# BEP31_final_kopie.net
KiCad netlist of a schematic drawn in EAGLE
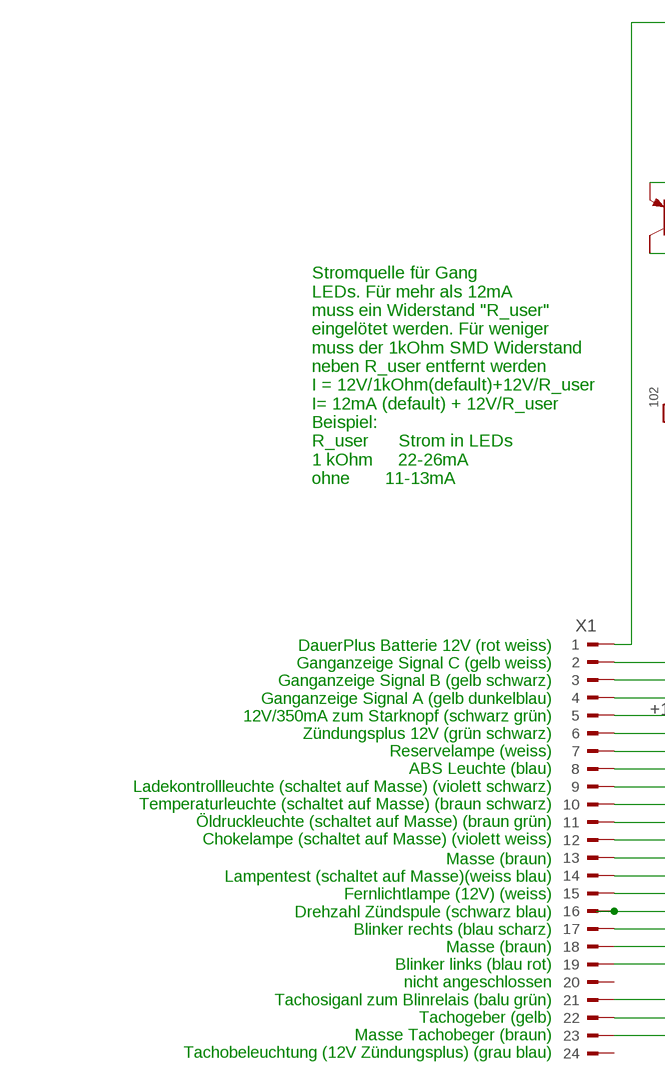
[diagram p0: schematic, sheet 1, part 1 of 2]
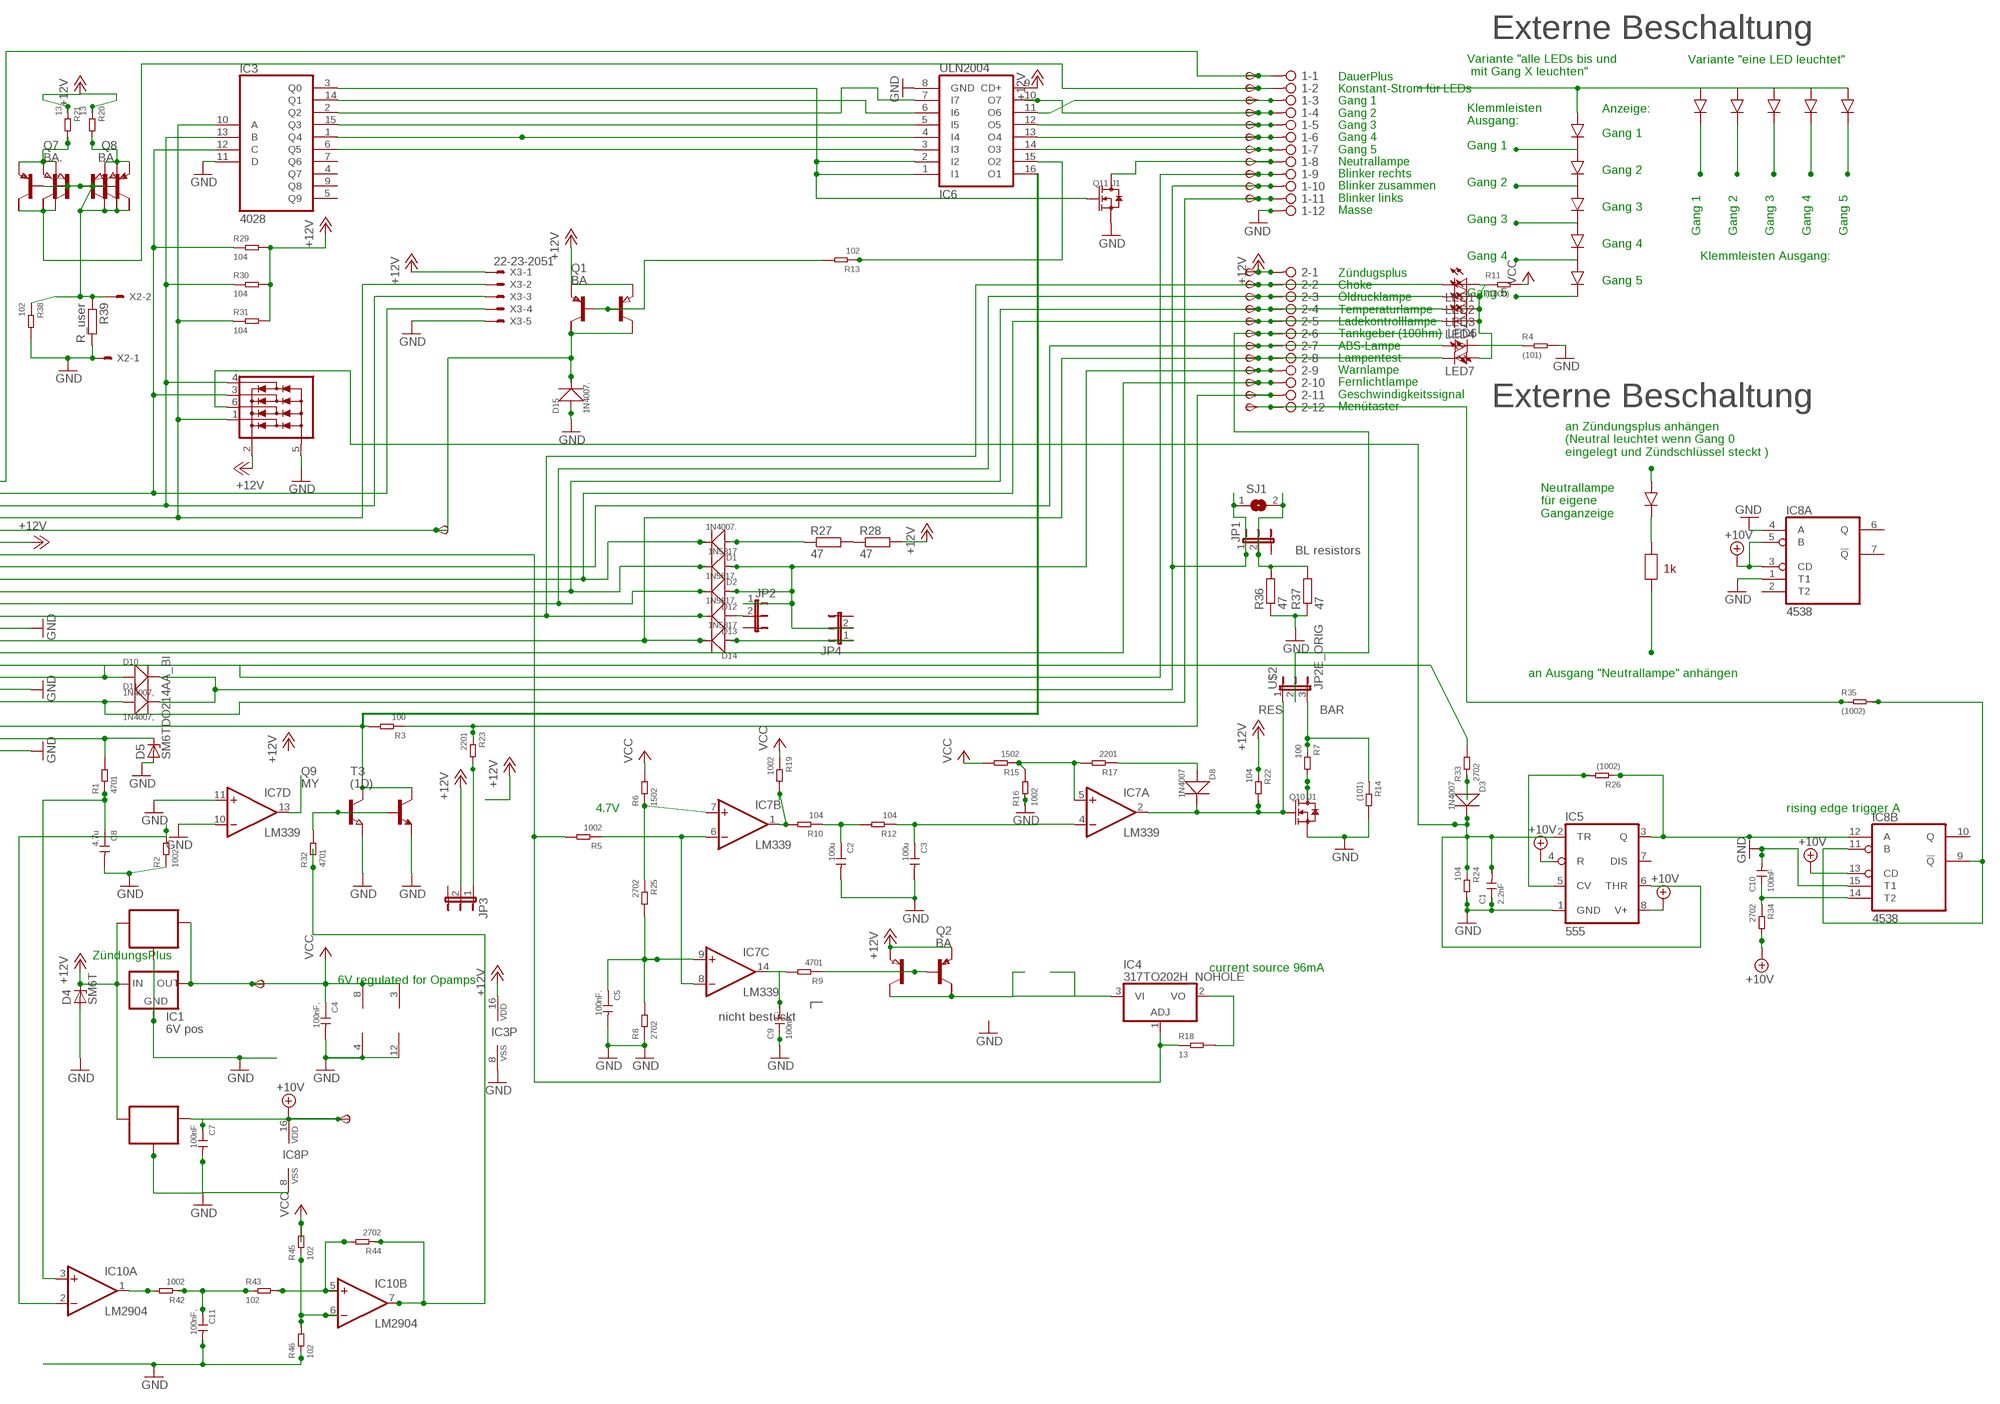
[diagram p1: schematic, sheet 1, part 2 of 2]

(export (version "E")
  (design (tool "Eeschema 10.0.6"))
  (components
    (comp (ref "1")
      (value "2081-1132")
      (footprint "eagle-import:12-PIN")
      (libsource (lib "eagle-import") (part "2081-1132"))
    )
    (comp (ref "2")
      (value "2081-1132")
      (footprint "eagle-import:12-PIN")
      (libsource (lib "eagle-import") (part "2081-1132"))
    )
    (comp (ref "6V")
      (value "TPSB2.0")
      (footprint "eagle-import:B2.0")
      (libsource (lib "eagle-import") (part "TPSB2.0"))
    )
    (comp (ref "10V")
      (value "TPSB2.0")
      (footprint "eagle-import:B2.0")
      (libsource (lib "eagle-import") (part "TPSB2.0"))
    )
    (comp (ref "C1")
      (value "2.2nF")
      (footprint "eagle-import:C0805")
      (fields (field (name "MPN") "CC0805KRX7R9BB104"))
      (libsource (lib "eagle-import") (part "CERAMIC-100NF-50V-10%-X7R(0805)"))
    )
    (comp (ref "C2")
      (value "100u")
      (footprint "eagle-import:C1206")
      (fields (field (name "MPN") "GRM31CR60J107ME39L"))
      (libsource (lib "eagle-import") (part "CERAMIC-100UF-6.3V-20%-X5R(1206)"))
    )
    (comp (ref "C3")
      (value "100u")
      (footprint "eagle-import:C1206")
      (fields (field (name "MPN") "GRM31CR60J107ME39L"))
      (libsource (lib "eagle-import") (part "CERAMIC-100UF-6.3V-20%-X5R(1206)"))
    )
    (comp (ref "C4")
      (value "100nF,")
      (footprint "eagle-import:C0805")
      (fields (field (name "MPN") "CC0805KRX7R9BB104"))
      (libsource (lib "eagle-import") (part "CERAMIC-100NF-50V-10%-X7R(0805)"))
    )
    (comp (ref "C5")
      (value "100nF.")
      (footprint "eagle-import:C0805")
      (fields (field (name "MPN") "CC0805KRX7R9BB104"))
      (libsource (lib "eagle-import") (part "CERAMIC-100NF-50V-10%-X7R(0805)"))
    )
    (comp (ref "C7")
      (value "100nF")
      (footprint "eagle-import:C0805")
      (fields (field (name "MPN") "CC0805KRX7R9BB104"))
      (libsource (lib "eagle-import") (part "CERAMIC-100NF-50V-10%-X7R(0805)"))
    )
    (comp (ref "C8")
      (value "4.7u")
      (footprint "eagle-import:C0805")
      (fields (field (name "MPN") "CC0805KKX5R8BB475"))
      (libsource (lib "eagle-import") (part "CERAMIC-4.7UF-25V-10%-X5R(0805)"))
    )
    (comp (ref "C9")
      (value "100nF.")
      (footprint "eagle-import:C0805")
      (fields (field (name "MPN") "CC0805KRX7R9BB104"))
      (libsource (lib "eagle-import") (part "CERAMIC-100NF-50V-10%-X7R(0805)"))
    )
    (comp (ref "C10")
      (value "100nF")
      (footprint "eagle-import:C0805")
      (fields (field (name "MPN") "CC0805KRX7R9BB104"))
      (libsource (lib "eagle-import") (part "CERAMIC-100NF-50V-10%-X7R(0805)"))
    )
    (comp (ref "C11")
      (value "100nF,")
      (footprint "eagle-import:C0805")
      (fields (field (name "MPN") "CC0805KRX7R9BB104"))
      (libsource (lib "eagle-import") (part "CERAMIC-100NF-50V-10%-X7R(0805)"))
    )
    (comp (ref "D1")
      (value "1N4007.")
      (footprint "eagle-import:DO-214AC")
      (fields (field (name "MPN") "1N4007"))
      (libsource (lib "eagle-import") (part "DIODE-GEN-PURPOSE-1KV-1A(DO-214AC)"))
    )
    (comp (ref "D2")
      (value "1N5817")
      (footprint "eagle-import:DO-214AC_SLIM")
      (libsource (lib "eagle-import") (part "DIODE-GEN-PURPOSE-1KV-1A(DO-214AC)DO-214AC/1206"))
    )
    (comp (ref "D3")
      (value "1N4007")
      (footprint "eagle-import:DO-214AC")
      (libsource (lib "eagle-import") (part "DIODE-GEN-PURPOSE-1KV-1A(DO-214AC)"))
    )
    (comp (ref "D4")
      (value "SM6T")
      (footprint "eagle-import:DO214AA")
      (libsource (lib "eagle-import") (part "SM6T"))
    )
    (comp (ref "D5")
      (value "SM6TDO214AA_BI")
      (footprint "eagle-import:DO214AA_BI")
      (libsource (lib "eagle-import") (part "SM6TDO214AA_BI"))
    )
    (comp (ref "D8")
      (value "1N4007")
      (footprint "eagle-import:DO-214AC")
      (libsource (lib "eagle-import") (part "DIODE-GEN-PURPOSE-1KV-1A(DO-214AC)"))
    )
    (comp (ref "D10")
      (value "1N4007,")
      (footprint "eagle-import:DO-214AC")
      (fields (field (name "MPN") "1N4007"))
      (libsource (lib "eagle-import") (part "DIODE-GEN-PURPOSE-1KV-1A(DO-214AC)"))
    )
    (comp (ref "D11")
      (value "1N4007,")
      (footprint "eagle-import:DO-214AC")
      (fields (field (name "MPN") "1N4007"))
      (libsource (lib "eagle-import") (part "DIODE-GEN-PURPOSE-1KV-1A(DO-214AC)"))
    )
    (comp (ref "D12")
      (value "1N5817.")
      (footprint "eagle-import:DO-214AC_SLIM")
      (libsource (lib "eagle-import") (part "DIODE-GEN-PURPOSE-1KV-1A(DO-214AC)DO-214AC/1206"))
    )
    (comp (ref "D13")
      (value "1N5817.")
      (footprint "eagle-import:DO-214AC_SLIM")
      (libsource (lib "eagle-import") (part "DIODE-GEN-PURPOSE-1KV-1A(DO-214AC)DO-214AC/1206"))
    )
    (comp (ref "D14")
      (value "1N5817")
      (footprint "eagle-import:DO-214AC_SLIM")
      (libsource (lib "eagle-import") (part "DIODE-GEN-PURPOSE-1KV-1A(DO-214AC)DO-214AC/1206"))
    )
    (comp (ref "D15")
      (value "1N4007.")
      (footprint "eagle-import:DO-214AC")
      (fields (field (name "MPN") "1N4007"))
      (libsource (lib "eagle-import") (part "DIODE-GEN-PURPOSE-1KV-1A(DO-214AC)"))
    )
    (comp (ref "IC1")
      (value "6V pos")
      (footprint "eagle-import:78LXX")
      (libsource (lib "eagle-import") (part "v-reg_78LXX"))
    )
    (comp (ref "IC2")
      (value "78L06")
      (footprint "eagle-import:SOT89_ROUND")
      (libsource (lib "eagle-import") (part "78LXXSOT89_ROUND"))
    )
    (comp (ref "IC3")
      (value "4028")
      (footprint "eagle-import:SO16")
      (libsource (lib "eagle-import") (part "4028D"))
    )
    (comp (ref "IC4")
      (value "317TO202H_NOHOLE")
      (footprint "eagle-import:TO220H_NOHOLE")
      (libsource (lib "eagle-import") (part "317TO202H_NOHOLE"))
    )
    (comp (ref "IC5")
      (value "555")
      (footprint "eagle-import:SO08")
      (libsource (lib "eagle-import") (part "555DNE"))
    )
    (comp (ref "IC6")
      (value "ULN2004")
      (footprint "eagle-import:SO16")
      (libsource (lib "eagle-import") (part "ULN2004AD"))
    )
    (comp (ref "IC7")
      (value "LM339")
      (footprint "eagle-import:SO14")
      (libsource (lib "eagle-import") (part "LM339D"))
    )
    (comp (ref "IC8")
      (value "4538")
      (footprint "eagle-import:SO16")
      (libsource (lib "eagle-import") (part "4538D"))
    )
    (comp (ref "IC9")
      (value "78L10")
      (footprint "eagle-import:SOT89_ROUND")
      (libsource (lib "eagle-import") (part "78LXXSOT89_ROUND"))
    )
    (comp (ref "IC10")
      (value "LM2904")
      (footprint "eagle-import:SO08")
      (libsource (lib "eagle-import") (part "LM358D"))
    )
    (comp (ref "JP1")
      (value "JP2EJP2_SMALLPADS")
      (footprint "eagle-import:JP2_SMALLPADS")
      (libsource (lib "eagle-import") (part "JP2EJP2_SMALLPADS"))
    )
    (comp (ref "JP2")
      (value "JP2EJP2_SMALLPADS")
      (footprint "eagle-import:JP2_SMALLPADS")
      (libsource (lib "eagle-import") (part "JP2EJP2_SMALLPADS"))
    )
    (comp (ref "JP3")
      (value "JP2EJP2_SMALLPADS")
      (footprint "eagle-import:JP2_SMALLPADS")
      (libsource (lib "eagle-import") (part "JP2EJP2_SMALLPADS"))
    )
    (comp (ref "JP4")
      (value "JP2EJP2_SMALLPADS")
      (footprint "eagle-import:JP2_SMALLPADS")
      (libsource (lib "eagle-import") (part "JP2EJP2_SMALLPADS"))
    )
    (comp (ref "LED1")
      (value "LEDLD260")
      (footprint "eagle-import:LD260")
      (libsource (lib "eagle-import") (part "LEDLD260"))
    )
    (comp (ref "LED2")
      (value "LEDLD260")
      (footprint "eagle-import:LD260")
      (libsource (lib "eagle-import") (part "LEDLD260"))
    )
    (comp (ref "LED3")
      (value "LEDLD260")
      (footprint "eagle-import:LD260")
      (libsource (lib "eagle-import") (part "LEDLD260"))
    )
    (comp (ref "LED4")
      (value "LEDLD260")
      (footprint "eagle-import:LD260")
      (libsource (lib "eagle-import") (part "LEDLD260"))
    )
    (comp (ref "LED6")
      (value "LEDLD260")
      (footprint "eagle-import:LD260")
      (libsource (lib "eagle-import") (part "LEDLD260"))
    )
    (comp (ref "LED7")
      (value "LEDLD260")
      (footprint "eagle-import:LD260")
      (libsource (lib "eagle-import") (part "LEDLD260"))
    )
    (comp (ref "Q1")
      (value "BA")
      (footprint "eagle-import:SOT89")
      (libsource (lib "eagle-import") (part "PNP-TRANSISTOR_SOT89"))
    )
    (comp (ref "Q2")
      (value "BA")
      (footprint "eagle-import:SOT89")
      (libsource (lib "eagle-import") (part "PNP-TRANSISTOR_SOT89"))
    )
    (comp (ref "Q3")
      (value "AH-16")
      (footprint "eagle-import:SOT223")
      (libsource (lib "eagle-import") (part "BCP53T1"))
    )
    (comp (ref "Q4")
      (value "(AH-16)")
      (footprint "eagle-import:SOT223")
      (libsource (lib "eagle-import") (part "BCP53T1"))
    )
    (comp (ref "Q5")
      (value "(AH-16)")
      (footprint "eagle-import:SOT223")
      (libsource (lib "eagle-import") (part "BCP53T1"))
    )
    (comp (ref "Q6")
      (value "(AH-16)")
      (footprint "eagle-import:SOT223")
      (libsource (lib "eagle-import") (part "BCP53T1"))
    )
    (comp (ref "Q7")
      (value "BA.")
      (footprint "eagle-import:SOT89")
      (libsource (lib "eagle-import") (part "PNP-TRANSISTOR_SOT89"))
    )
    (comp (ref "Q8")
      (value "BA.")
      (footprint "eagle-import:SOT89")
      (libsource (lib "eagle-import") (part "PNP-TRANSISTOR_SOT89"))
    )
    (comp (ref "Q9")
      (value "MY")
      (footprint "eagle-import:SOT89")
      (libsource (lib "eagle-import") (part "NPN-TRANSISTOR_SOT89"))
    )
    (comp (ref "Q10")
      (value "J1")
      (footprint "eagle-import:SOT-23")
      (fields (field (name "MPN") "BSS138W-7-F"))
      (libsource (lib "eagle-import") (part "SMD-MOSFET-N-CH-50V-200MA-BSS138W-7-F(SOT-23)"))
    )
    (comp (ref "Q11")
      (value "J1")
      (footprint "eagle-import:SOT-23")
      (fields (field (name "MPN") "BSS138W-7-F"))
      (libsource (lib "eagle-import") (part "SMD-MOSFET-N-CH-50V-200MA-BSS138W-7-F(SOT-23)"))
    )
    (comp (ref "R1")
      (value "4701")
      (footprint "eagle-import:R0805")
      (fields (field (name "MPN") "RC0805JR-074K7L"))
      (libsource (lib "eagle-import") (part "SMD-RES-4.7K-5%-1/8W(0805)"))
    )
    (comp (ref "R2")
      (value "1002")
      (footprint "eagle-import:R0805")
      (fields (field (name "MPN") "RC0805FR-0710KL"))
      (libsource (lib "eagle-import") (part "SMD-RES-10K-1%-1/8W(0805)"))
    )
    (comp (ref "R3")
      (value "100")
      (footprint "eagle-import:R0805")
      (fields (field (name "MPN") "RC0805JR-07220RL"))
      (libsource (lib "eagle-import") (part "SMD-RES-220R-5%-1/8W(0805)"))
    )
    (comp (ref "R4")
      (value "(101)")
      (footprint "eagle-import:R0805")
      (fields (field (name "MPN") "RC0805JR-07100RL"))
      (libsource (lib "eagle-import") (part "SMD-RES-100R-5%-1/8W(0805)"))
    )
    (comp (ref "R5")
      (value "1002")
      (footprint "eagle-import:R0805")
      (fields (field (name "MPN") "RC0805FR-0710KL"))
      (libsource (lib "eagle-import") (part "SMD-RES-10K-1%-1/8W(0805)"))
    )
    (comp (ref "R6")
      (value "1502")
      (footprint "eagle-import:R0805")
      (fields (field (name "MPN") "RC0805FR-0710KL"))
      (libsource (lib "eagle-import") (part "SMD-RES-10K-1%-1/8W(0805)"))
    )
    (comp (ref "R7")
      (value "100")
      (footprint "eagle-import:R0805")
      (fields (field (name "MPN") "RC0805JR-072K2L"))
      (libsource (lib "eagle-import") (part "SMD-RES-2.2K-5%-1/8W(0805)"))
    )
    (comp (ref "R8")
      (value "2702")
      (footprint "eagle-import:R0805")
      (fields (field (name "MPN") "RC0805JR-074K7L"))
      (libsource (lib "eagle-import") (part "SMD-RES-4.7K-5%-1/8W(0805)"))
    )
    (comp (ref "R9")
      (value "4701")
      (footprint "eagle-import:R0805")
      (fields (field (name "MPN") "RC0805JR-074K7L"))
      (libsource (lib "eagle-import") (part "SMD-RES-4.7K-5%-1/8W(0805)"))
    )
    (comp (ref "R10")
      (value "104")
      (footprint "eagle-import:R0805")
      (fields (field (name "MPN") "RC0805FR-0710KL"))
      (libsource (lib "eagle-import") (part "SMD-RES-10K-1%-1/8W(0805)"))
    )
    (comp (ref "R11")
      (value "(1000)")
      (footprint "eagle-import:R0805")
      (fields (field (name "MPN") "RC0805JR-07100RL"))
      (libsource (lib "eagle-import") (part "SMD-RES-100R-5%-1/8W(0805)"))
    )
    (comp (ref "R12")
      (value "104")
      (footprint "eagle-import:R0805")
      (fields (field (name "MPN") "RC0805FR-0710KL"))
      (libsource (lib "eagle-import") (part "SMD-RES-10K-1%-1/8W(0805)"))
    )
    (comp (ref "R13")
      (value "102")
      (footprint "eagle-import:R0805")
      (fields (field (name "MPN") "RC0805JR-071KL"))
      (libsource (lib "eagle-import") (part "SMD-RES-1K-5%-1/8W(0805)"))
    )
    (comp (ref "R14")
      (value "(101)")
      (footprint "eagle-import:R0805")
      (fields (field (name "MPN") "RC0805JR-072K2L"))
      (libsource (lib "eagle-import") (part "SMD-RES-2.2K-5%-1/8W(0805)"))
    )
    (comp (ref "R15")
      (value "1502")
      (footprint "eagle-import:R0805")
      (fields (field (name "MPN") "RC0805FR-0710KL"))
      (libsource (lib "eagle-import") (part "SMD-RES-10K-1%-1/8W(0805)"))
    )
    (comp (ref "R16")
      (value "1002")
      (footprint "eagle-import:R0805")
      (fields (field (name "MPN") "RC0805FR-0710KL"))
      (libsource (lib "eagle-import") (part "SMD-RES-10K-1%-1/8W(0805)"))
    )
    (comp (ref "R17")
      (value "2201")
      (footprint "eagle-import:R0805")
      (fields (field (name "MPN") "RC0805JR-072K2L"))
      (libsource (lib "eagle-import") (part "SMD-RES-2.2K-5%-1/8W(0805)"))
    )
    (comp (ref "R18")
      (value "13")
      (footprint "eagle-import:R1206")
      (fields (field (name "MPN") "RC1206JR-0713RL"))
      (libsource (lib "eagle-import") (part "SMD-RES-13R-5%-1/4W(1206)"))
    )
    (comp (ref "R19")
      (value "1002")
      (footprint "eagle-import:R0805")
      (fields (field (name "MPN") "RC0805FR-0710KL"))
      (libsource (lib "eagle-import") (part "SMD-RES-10K-1%-1/8W(0805)"))
    )
    (comp (ref "R20")
      (value "13")
      (footprint "eagle-import:R1206")
      (fields (field (name "MPN") "RC1206JR-0713RL"))
      (libsource (lib "eagle-import") (part "SMD-RES-13R-5%-1/4W(1206)"))
    )
    (comp (ref "R21")
      (value "13")
      (footprint "eagle-import:R1206")
      (fields (field (name "MPN") "RC1206JR-0713RL"))
      (libsource (lib "eagle-import") (part "SMD-RES-13R-5%-1/4W(1206)"))
    )
    (comp (ref "R22")
      (value "104")
      (footprint "eagle-import:R0805")
      (fields (field (name "MPN") "RC0805FR-0710KL"))
      (libsource (lib "eagle-import") (part "SMD-RES-10K-1%-1/8W(0805)"))
    )
    (comp (ref "R23")
      (value "2201")
      (footprint "eagle-import:R0805")
      (fields (field (name "MPN") "RC0805JR-072K2L"))
      (libsource (lib "eagle-import") (part "SMD-RES-2.2K-5%-1/8W(0805)"))
    )
    (comp (ref "R24")
      (value "104")
      (footprint "eagle-import:R0805")
      (fields (field (name "MPN") "RC0805FR-0710KL"))
      (libsource (lib "eagle-import") (part "SMD-RES-10K-1%-1/8W(0805)"))
    )
    (comp (ref "R25")
      (value "2702")
      (footprint "eagle-import:R0805")
      (fields (field (name "MPN") "RC0805JR-074K7L"))
      (libsource (lib "eagle-import") (part "SMD-RES-4.7K-5%-1/8W(0805)"))
    )
    (comp (ref "R26")
      (value "(1002)")
      (footprint "eagle-import:R0805")
      (fields (field (name "MPN") "RC0805FR-0710KL"))
      (libsource (lib "eagle-import") (part "SMD-RES-10K-1%-1/8W(0805)"))
    )
    (comp (ref "R27")
      (value "47")
      (footprint "eagle-import:V235_17_1MM")
      (libsource (lib "eagle-import") (part "R-EU_V235/17_1MM"))
    )
    (comp (ref "R28")
      (value "47")
      (footprint "eagle-import:V235_17_1MM")
      (libsource (lib "eagle-import") (part "R-EU_V235/17_1MM"))
    )
    (comp (ref "R29")
      (value "104")
      (footprint "eagle-import:R0805")
      (fields (field (name "MPN") "RC0805FR-0710KL"))
      (libsource (lib "eagle-import") (part "SMD-RES-10K-1%-1/8W(0805)"))
    )
    (comp (ref "R30")
      (value "104")
      (footprint "eagle-import:R0805")
      (fields (field (name "MPN") "RC0805FR-0710KL"))
      (libsource (lib "eagle-import") (part "SMD-RES-10K-1%-1/8W(0805)"))
    )
    (comp (ref "R31")
      (value "104")
      (footprint "eagle-import:R0805")
      (fields (field (name "MPN") "RC0805FR-0710KL"))
      (libsource (lib "eagle-import") (part "SMD-RES-10K-1%-1/8W(0805)"))
    )
    (comp (ref "R32")
      (value "4701")
      (footprint "eagle-import:R0805")
      (fields (field (name "MPN") "RC0805JR-074K7L"))
      (libsource (lib "eagle-import") (part "SMD-RES-4.7K-5%-1/8W(0805)"))
    )
    (comp (ref "R33")
      (value "2702")
      (footprint "eagle-import:R0805")
      (fields (field (name "MPN") "RC0805FR-0710KL"))
      (libsource (lib "eagle-import") (part "SMD-RES-10K-1%-1/8W(0805)"))
    )
    (comp (ref "R34")
      (value "2702")
      (footprint "eagle-import:R0805")
      (fields (field (name "MPN") "RC0805JR-074K7L"))
      (libsource (lib "eagle-import") (part "SMD-RES-4.7K-5%-1/8W(0805)"))
    )
    (comp (ref "R35")
      (value "(1002)")
      (footprint "eagle-import:R0805")
      (fields (field (name "MPN") "RC0805JR-074K7L"))
      (libsource (lib "eagle-import") (part "SMD-RES-4.7K-5%-1/8W(0805)"))
    )
    (comp (ref "R36")
      (value "47")
      (footprint "eagle-import:V235_17_1MM")
      (libsource (lib "eagle-import") (part "R-EU_V235/17_1MM"))
    )
    (comp (ref "R37")
      (value "47")
      (footprint "eagle-import:V235_17_1MM")
      (libsource (lib "eagle-import") (part "R-EU_V235/17_1MM"))
    )
    (comp (ref "R38")
      (value "102")
      (footprint "eagle-import:R0805")
      (fields (field (name "MPN") "RC0805JR-071KL"))
      (libsource (lib "eagle-import") (part "SMD-RES-1K-5%-1/8W(0805)"))
    )
    (comp (ref "R39")
      (value "R_user")
      (footprint "eagle-import:R0805")
      (libsource (lib "eagle-import") (part "R-EU_R0805"))
    )
    (comp (ref "R42")
      (value "1002")
      (footprint "eagle-import:R0805")
      (fields (field (name "MPN") "RC0805FR-0710KL"))
      (libsource (lib "eagle-import") (part "SMD-RES-10K-1%-1/8W(0805)"))
    )
    (comp (ref "R43")
      (value "102")
      (footprint "eagle-import:R0805")
      (fields (field (name "MPN") "RC0805JR-071KL"))
      (libsource (lib "eagle-import") (part "SMD-RES-1K-5%-1/8W(0805)"))
    )
    (comp (ref "R44")
      (value "2702")
      (footprint "eagle-import:R0805")
      (fields (field (name "MPN") "RC0805JR-074K7L"))
      (libsource (lib "eagle-import") (part "SMD-RES-4.7K-5%-1/8W(0805)"))
    )
    (comp (ref "R45")
      (value "102")
      (footprint "eagle-import:R0805")
      (fields (field (name "MPN") "RC0805JR-071KL"))
      (libsource (lib "eagle-import") (part "SMD-RES-1K-5%-1/8W(0805)"))
    )
    (comp (ref "R46")
      (value "102")
      (footprint "eagle-import:R0805")
      (fields (field (name "MPN") "RC0805JR-071KL"))
      (libsource (lib "eagle-import") (part "SMD-RES-1K-5%-1/8W(0805)"))
    )
    (comp (ref "SJ1") (value "SJ") (footprint "eagle-import:SJ") (libsource (lib "eagle-import") (part "SJ")))
    (comp (ref "START")
      (value "TPSB2.0")
      (footprint "eagle-import:B2.0")
      (libsource (lib "eagle-import") (part "TPSB2.0"))
    )
    (comp (ref "T1")
      (value "PNP2SM8")
      (footprint "eagle-import:SM8")
      (libsource (lib "eagle-import") (part "PNP2SM8"))
    )
    (comp (ref "T3")
      (value "(1D)")
      (footprint "eagle-import:SOT23-BEC")
      (libsource (lib "eagle-import") (part "-NPN-SOT23-BECMMBTA42LT1"))
    )
    (comp (ref "TP1")
      (value "TPSB2.0")
      (footprint "eagle-import:B2.0")
      (libsource (lib "eagle-import") (part "TPSB2.0"))
    )
    (comp (ref "TP2")
      (value "TPSB2.0")
      (footprint "eagle-import:B2.0")
      (libsource (lib "eagle-import") (part "TPSB2.0"))
    )
    (comp (ref "TP3")
      (value "TPSB2.0")
      (footprint "eagle-import:B2.0")
      (libsource (lib "eagle-import") (part "TPSB2.0"))
    )
    (comp (ref "TP4")
      (value "TPSB2.0")
      (footprint "eagle-import:B2.0")
      (libsource (lib "eagle-import") (part "TPSB2.0"))
    )
    (comp (ref "TP5")
      (value "TPSB2.0")
      (footprint "eagle-import:B2.0")
      (libsource (lib "eagle-import") (part "TPSB2.0"))
    )
    (comp (ref "TP6")
      (value "TPSB2.0")
      (footprint "eagle-import:B2.0")
      (libsource (lib "eagle-import") (part "TPSB2.0"))
    )
    (comp (ref "TP7")
      (value "TPSB2.0")
      (footprint "eagle-import:B2.0")
      (libsource (lib "eagle-import") (part "TPSB2.0"))
    )
    (comp (ref "TP8")
      (value "TPSB2.0")
      (footprint "eagle-import:B2.0")
      (libsource (lib "eagle-import") (part "TPSB2.0"))
    )
    (comp (ref "TP9")
      (value "TPSB2.0")
      (footprint "eagle-import:B2.0")
      (libsource (lib "eagle-import") (part "TPSB2.0"))
    )
    (comp (ref "TP10")
      (value "TPSB2.0")
      (footprint "eagle-import:B2.0")
      (libsource (lib "eagle-import") (part "TPSB2.0"))
    )
    (comp (ref "TP11")
      (value "TPSB2.0")
      (footprint "eagle-import:B2.0")
      (libsource (lib "eagle-import") (part "TPSB2.0"))
    )
    (comp (ref "TP12")
      (value "TPSB2.0")
      (footprint "eagle-import:B2.0")
      (libsource (lib "eagle-import") (part "TPSB2.0"))
    )
    (comp (ref "TP13")
      (value "TPSB2.0")
      (footprint "eagle-import:B2.0")
      (libsource (lib "eagle-import") (part "TPSB2.0"))
    )
    (comp (ref "TP16")
      (value "TPSB2.0")
      (footprint "eagle-import:B2.0")
      (libsource (lib "eagle-import") (part "TPSB2.0"))
    )
    (comp (ref "TP17")
      (value "TPSB2.0")
      (footprint "eagle-import:B2.0")
      (libsource (lib "eagle-import") (part "TPSB2.0"))
    )
    (comp (ref "TP18")
      (value "TPSB2.0")
      (footprint "eagle-import:B2.0")
      (libsource (lib "eagle-import") (part "TPSB2.0"))
    )
    (comp (ref "TP19")
      (value "TPSB2.0")
      (footprint "eagle-import:B2.0")
      (libsource (lib "eagle-import") (part "TPSB2.0"))
    )
    (comp (ref "TP21")
      (value "TPSB2.0")
      (footprint "eagle-import:B2.0")
      (libsource (lib "eagle-import") (part "TPSB2.0"))
    )
    (comp (ref "TP22")
      (value "TPSB2.0")
      (footprint "eagle-import:B2.0")
      (libsource (lib "eagle-import") (part "TPSB2.0"))
    )
    (comp (ref "TP23")
      (value "TPSB2.0")
      (footprint "eagle-import:B2.0")
      (libsource (lib "eagle-import") (part "TPSB2.0"))
    )
    (comp (ref "TP24")
      (value "TPSB1,27")
      (footprint "eagle-import:B1,27")
      (libsource (lib "eagle-import") (part "TPSB1,27"))
    )
    (comp (ref "TP25")
      (value "TPSB2.0")
      (footprint "eagle-import:B2.0")
      (libsource (lib "eagle-import") (part "TPSB2.0"))
    )
    (comp (ref "TP26")
      (value "TPSB2.0")
      (footprint "eagle-import:B2.0")
      (libsource (lib "eagle-import") (part "TPSB2.0"))
    )
    (comp (ref "U$2")
      (value "JP2E_ORIG")
      (footprint "eagle-import:JP2_ORIG_SMALLPADS")
      (libsource (lib "eagle-import") (part "JP2E_ORIG"))
    )
    (comp (ref "U$3")
      (value "NUP4304SOT457_R")
      (footprint "eagle-import:SOT457R_PHILIPS")
      (libsource (lib "eagle-import") (part "NUP4304SOT457_R"))
    )
    (comp (ref "X1")
      (value "CON_BMWV2")
      (footprint "eagle-import:24-PIN_V2")
      (libsource (lib "eagle-import") (part "CON_BMWV2"))
    )
    (comp (ref "X2")
      (value "22-23-2021")
      (footprint "eagle-import:22-23-2021")
      (fields (field (name "MF") "MOLEX"))
      (libsource (lib "eagle-import") (part "22-23-2021"))
    )
    (comp (ref "X3")
      (value "22-23-2051")
      (footprint "eagle-import:22-23-2051")
      (fields (field (name "MF") "MOLEX"))
      (libsource (lib "eagle-import") (part "22-23-2051"))
    )
  )
  (nets
    (net (code "1") (name "+10V") (class "Default")
      (node (ref "10V") (pin "TP") (pinfunction "PP_TP") (pintype "input"))
      (node (ref "C7") (pin "1") (pinfunction "1_1") (pintype "passive"))
      (node (ref "IC5") (pin "4") (pinfunction "R_4") (pintype "input"))
      (node (ref "IC5") (pin "8") (pinfunction "V+_8") (pintype "power_in"))
      (node (ref "IC8") (pin "13") (pinfunction "CD_13") (pintype "input"))
      (node (ref "IC8") (pin "16") (pinfunction "VDD_16") (pintype "power_in"))
      (node (ref "IC8") (pin "3") (pinfunction "CD_3") (pintype "input"))
      (node (ref "IC8") (pin "5") (pinfunction "B_5") (pintype "input"))
      (node (ref "IC9") (pin "1") (pinfunction "OUT_1") (pintype "passive"))
      (node (ref "R34") (pin "2") (pinfunction "2_2") (pintype "passive"))
    )
    (net (code "2") (name "+12V") (class "Default")
      (node (ref "2") (pin "1") (pinfunction "KL_1") (pintype "passive"))
      (node (ref "D4") (pin "C") (pinfunction "C_C") (pintype "passive"))
      (node (ref "IC1") (pin "IN") (pinfunction "IN_IN") (pintype "input"))
      (node (ref "IC2") (pin "3") (pinfunction "IN_3") (pintype "input"))
      (node (ref "IC3") (pin "16") (pinfunction "VDD_16") (pintype "power_in"))
      (node (ref "IC6") (pin "9") (pinfunction "CD+_9") (pintype "passive"))
      (node (ref "IC9") (pin "3") (pinfunction "IN_3") (pintype "input"))
      (node (ref "JP3") (pin "2") (pinfunction "2_2") (pintype "passive"))
      (node (ref "Q1") (pin "3") (pinfunction "E_3") (pintype "passive"))
      (node (ref "Q2") (pin "3") (pinfunction "E_3") (pintype "passive"))
      (node (ref "Q3") (pin "3") (pinfunction "E_3") (pintype "passive"))
      (node (ref "Q4") (pin "3") (pinfunction "E_3") (pintype "passive"))
      (node (ref "R20") (pin "1") (pinfunction "1_1") (pintype "passive"))
      (node (ref "R21") (pin "1") (pinfunction "1_1") (pintype "passive"))
      (node (ref "R22") (pin "1") (pinfunction "1_1") (pintype "passive"))
      (node (ref "R28") (pin "2") (pinfunction "2_2") (pintype "passive"))
      (node (ref "R29") (pin "2") (pinfunction "2_2") (pintype "passive"))
      (node (ref "R30") (pin "2") (pinfunction "2_2") (pintype "passive"))
      (node (ref "R31") (pin "2") (pinfunction "2_2") (pintype "passive"))
      (node (ref "TP12") (pin "TP") (pinfunction "PP_TP") (pintype "input"))
      (node (ref "U$3") (pin "2") (pinfunction "V+_2") (pintype "passive"))
      (node (ref "X1") (pin "6") (pinfunction "6_6") (pintype "passive"))
      (node (ref "X3") (pin "1") (pinfunction "S_1") (pintype "passive"))
    )
    (net (code "3") (name "GND") (class "Default")
      (node (ref "1") (pin "12") (pinfunction "KL_12") (pintype "passive"))
      (node (ref "C1") (pin "1") (pinfunction "1_1") (pintype "passive"))
      (node (ref "C10") (pin "2") (pinfunction "2_2") (pintype "passive"))
      (node (ref "C11") (pin "2") (pinfunction "2_2") (pintype "passive"))
      (node (ref "C2") (pin "2") (pinfunction "2_2") (pintype "passive"))
      (node (ref "C3") (pin "2") (pinfunction "2_2") (pintype "passive"))
      (node (ref "C4") (pin "2") (pinfunction "2_2") (pintype "passive"))
      (node (ref "C5") (pin "2") (pinfunction "2_2") (pintype "passive"))
      (node (ref "C7") (pin "2") (pinfunction "2_2") (pintype "passive"))
      (node (ref "C8") (pin "2") (pinfunction "2_2") (pintype "passive"))
      (node (ref "C9") (pin "1") (pinfunction "1_1") (pintype "passive"))
      (node (ref "D15") (pin "1") (pinfunction "+_1") (pintype "passive"))
      (node (ref "D4") (pin "A") (pinfunction "A_A") (pintype "passive"))
      (node (ref "D5") (pin "A") (pinfunction "A_A") (pintype "passive"))
      (node (ref "IC1") (pin "GND") (pinfunction "GND_GND") (pintype "input"))
      (node (ref "IC10") (pin "4") (pinfunction "V-_4") (pintype "power_in"))
      (node (ref "IC2") (pin "2") (pinfunction "GND_2") (pintype "input"))
      (node (ref "IC2") (pin "2@1") (pinfunction "GND_2@1") (pintype "input"))
      (node (ref "IC3") (pin "11") (pinfunction "D_11") (pintype "input"))
      (node (ref "IC3") (pin "8") (pinfunction "VSS_8") (pintype "power_in"))
      (node (ref "IC5") (pin "1") (pinfunction "GND_1") (pintype "power_in"))
      (node (ref "IC6") (pin "8") (pinfunction "GND_8") (pintype "power_in"))
      (node (ref "IC7") (pin "10") (pinfunction "-IN_10") (pintype "input"))
      (node (ref "IC7") (pin "11") (pinfunction "+IN_11") (pintype "input"))
      (node (ref "IC7") (pin "12") (pinfunction "GND_12") (pintype "power_in"))
      (node (ref "IC8") (pin "1") (pinfunction "T1_1") (pintype "input"))
      (node (ref "IC8") (pin "15") (pinfunction "T1_15") (pintype "input"))
      (node (ref "IC8") (pin "4") (pinfunction "A_4") (pintype "input"))
      (node (ref "IC8") (pin "8") (pinfunction "VSS_8") (pintype "power_in"))
      (node (ref "IC9") (pin "2") (pinfunction "GND_2") (pintype "input"))
      (node (ref "IC9") (pin "2@1") (pinfunction "GND_2@1") (pintype "input"))
      (node (ref "Q10") (pin "2") (pinfunction "S_2") (pintype "passive"))
      (node (ref "Q11") (pin "2") (pinfunction "S_2") (pintype "passive"))
      (node (ref "Q9") (pin "3") (pinfunction "E_3") (pintype "passive"))
      (node (ref "R14") (pin "2") (pinfunction "2_2") (pintype "passive"))
      (node (ref "R16") (pin "1") (pinfunction "1_1") (pintype "passive"))
      (node (ref "R2") (pin "1") (pinfunction "1_1") (pintype "passive"))
      (node (ref "R24") (pin "2") (pinfunction "2_2") (pintype "passive"))
      (node (ref "R36") (pin "1") (pinfunction "1_1") (pintype "passive"))
      (node (ref "R37") (pin "1") (pinfunction "1_1") (pintype "passive"))
      (node (ref "R38") (pin "2") (pinfunction "2_2") (pintype "passive"))
      (node (ref "R39") (pin "2") (pinfunction "2_2") (pintype "passive"))
      (node (ref "R4") (pin "2") (pinfunction "2_2") (pintype "passive"))
      (node (ref "R46") (pin "1") (pinfunction "1_1") (pintype "passive"))
      (node (ref "R8") (pin "1") (pinfunction "1_1") (pintype "passive"))
      (node (ref "T3") (pin "E") (pinfunction "E_E") (pintype "passive"))
      (node (ref "U$3") (pin "5") (pinfunction "V-_5") (pintype "passive"))
      (node (ref "X1") (pin "13") (pinfunction "13_13") (pintype "passive"))
      (node (ref "X1") (pin "18") (pinfunction "18_18") (pintype "passive"))
      (node (ref "X1") (pin "23") (pinfunction "23_23") (pintype "passive"))
      (node (ref "X2") (pin "1") (pinfunction "S_1") (pintype "passive"))
      (node (ref "X3") (pin "5") (pinfunction "S_5") (pintype "passive"))
    )
    (net (code "4") (name "Net-(1A-KL)") (class "Default")
      (node (ref "1") (pin "1") (pinfunction "KL_1") (pintype "passive"))
      (node (ref "TP1") (pin "TP") (pinfunction "PP_TP") (pintype "input"))
      (node (ref "X1") (pin "1") (pinfunction "1_1") (pintype "passive"))
    )
    (net (code "5") (name "Net-(1B-KL)") (class "Default")
      (node (ref "1") (pin "10") (pinfunction "KL_10") (pintype "passive"))
      (node (ref "D10") (pin "2") (pinfunction "-_2") (pintype "passive"))
      (node (ref "D11") (pin "2") (pinfunction "-_2") (pintype "passive"))
      (node (ref "JP1") (pin "1") (pinfunction "1_1") (pintype "passive"))
      (node (ref "SJ1") (pin "1") (pinfunction "1_1") (pintype "passive"))
      (node (ref "TP10") (pin "TP") (pinfunction "PP_TP") (pintype "input"))
    )
    (net (code "6") (name "Net-(1C-KL)") (class "Default")
      (node (ref "1") (pin "11") (pinfunction "KL_11") (pintype "passive"))
      (node (ref "D11") (pin "1") (pinfunction "+_1") (pintype "passive"))
      (node (ref "TP11") (pin "TP") (pinfunction "PP_TP") (pintype "input"))
      (node (ref "X1") (pin "19") (pinfunction "19_19") (pintype "passive"))
    )
    (net (code "7") (name "Net-(1E-KL)") (class "Default")
      (node (ref "1") (pin "2") (pinfunction "KL_2") (pintype "passive"))
      (node (ref "Q5") (pin "2") (pinfunction "C_2") (pintype "passive"))
      (node (ref "Q8") (pin "2") (pinfunction "C_2") (pintype "passive"))
      (node (ref "T1") (pin "8") (pinfunction "C1_8") (pintype "passive"))
      (node (ref "TP2") (pin "TP") (pinfunction "PP_TP") (pintype "input"))
    )
    (net (code "8") (name "Net-(1F-KL)") (class "Default")
      (node (ref "1") (pin "3") (pinfunction "KL_3") (pintype "passive"))
      (node (ref "IC6") (pin "11") (pinfunction "O6_11") (pintype "open_collector"))
      (node (ref "TP3") (pin "TP") (pinfunction "PP_TP") (pintype "input"))
    )
    (net (code "9") (name "Net-(1G-KL)") (class "Default")
      (node (ref "1") (pin "4") (pinfunction "KL_4") (pintype "passive"))
      (node (ref "IC6") (pin "10") (pinfunction "O7_10") (pintype "open_collector"))
      (node (ref "TP4") (pin "TP") (pinfunction "PP_TP") (pintype "input"))
    )
    (net (code "10") (name "Net-(1H-KL)") (class "Default")
      (node (ref "1") (pin "5") (pinfunction "KL_5") (pintype "passive"))
      (node (ref "IC6") (pin "12") (pinfunction "O5_12") (pintype "open_collector"))
      (node (ref "TP5") (pin "TP") (pinfunction "PP_TP") (pintype "input"))
    )
    (net (code "11") (name "Net-(1I-KL)") (class "Default")
      (node (ref "1") (pin "6") (pinfunction "KL_6") (pintype "passive"))
      (node (ref "IC6") (pin "13") (pinfunction "O4_13") (pintype "open_collector"))
      (node (ref "TP6") (pin "TP") (pinfunction "PP_TP") (pintype "input"))
    )
    (net (code "12") (name "Net-(1J-KL)") (class "Default")
      (node (ref "1") (pin "7") (pinfunction "KL_7") (pintype "passive"))
      (node (ref "IC6") (pin "14") (pinfunction "O3_14") (pintype "open_collector"))
      (node (ref "TP7") (pin "TP") (pinfunction "PP_TP") (pintype "input"))
    )
    (net (code "13") (name "Net-(1K-KL)") (class "Default")
      (node (ref "1") (pin "8") (pinfunction "KL_8") (pintype "passive"))
      (node (ref "Q11") (pin "3") (pinfunction "D_3") (pintype "passive"))
      (node (ref "TP8") (pin "TP") (pinfunction "PP_TP") (pintype "input"))
    )
    (net (code "14") (name "Net-(1L-KL)") (class "Default")
      (node (ref "1") (pin "9") (pinfunction "KL_9") (pintype "passive"))
      (node (ref "D10") (pin "1") (pinfunction "+_1") (pintype "passive"))
      (node (ref "TP9") (pin "TP") (pinfunction "PP_TP") (pintype "input"))
      (node (ref "X1") (pin "17") (pinfunction "17_17") (pintype "passive"))
    )
    (net (code "15") (name "Net-(2B-KL)") (class "Default")
      (node (ref "2") (pin "10") (pinfunction "KL_10") (pintype "passive"))
      (node (ref "TP25") (pin "TP") (pinfunction "PP_TP") (pintype "input"))
      (node (ref "X1") (pin "15") (pinfunction "15_15") (pintype "passive"))
    )
    (net (code "16") (name "Net-(2C-KL)") (class "Default")
      (node (ref "2") (pin "11") (pinfunction "KL_11") (pintype "passive"))
      (node (ref "R23") (pin "1") (pinfunction "1_1") (pintype "passive"))
      (node (ref "R3") (pin "1") (pinfunction "1_1") (pintype "passive"))
      (node (ref "TP26") (pin "TP") (pinfunction "PP_TP") (pintype "input"))
    )
    (net (code "17") (name "Net-(2D-KL)") (class "Default")
      (node (ref "2") (pin "12") (pinfunction "KL_12") (pintype "passive"))
      (node (ref "R35") (pin "1") (pinfunction "1_1") (pintype "passive"))
      (node (ref "TP13") (pin "TP") (pinfunction "PP_TP") (pintype "input"))
    )
    (net (code "18") (name "Net-(2E-KL)") (class "Default")
      (node (ref "2") (pin "2") (pinfunction "KL_2") (pintype "passive"))
      (node (ref "D13") (pin "2") (pinfunction "-_2") (pintype "passive"))
      (node (ref "LED1") (pin "K") (pinfunction "C_K") (pintype "passive"))
      (node (ref "TP16") (pin "TP") (pinfunction "PP_TP") (pintype "input"))
      (node (ref "X1") (pin "12") (pinfunction "12_12") (pintype "passive"))
    )
    (net (code "19") (name "Net-(2F-KL)") (class "Default")
      (node (ref "2") (pin "3") (pinfunction "KL_3") (pintype "passive"))
      (node (ref "D12") (pin "2") (pinfunction "-_2") (pintype "passive"))
      (node (ref "LED2") (pin "K") (pinfunction "C_K") (pintype "passive"))
      (node (ref "TP17") (pin "TP") (pinfunction "PP_TP") (pintype "input"))
      (node (ref "X1") (pin "11") (pinfunction "11_11") (pintype "passive"))
    )
    (net (code "20") (name "Net-(2G-KL)") (class "Default")
      (node (ref "2") (pin "4") (pinfunction "KL_4") (pintype "passive"))
      (node (ref "D2") (pin "2") (pinfunction "-_2") (pintype "passive"))
      (node (ref "LED3") (pin "K") (pinfunction "C_K") (pintype "passive"))
      (node (ref "TP18") (pin "TP") (pinfunction "PP_TP") (pintype "input"))
      (node (ref "X1") (pin "10") (pinfunction "10_10") (pintype "passive"))
    )
    (net (code "21") (name "Net-(2H-KL)") (class "Default")
      (node (ref "2") (pin "5") (pinfunction "KL_5") (pintype "passive"))
      (node (ref "D1") (pin "2") (pinfunction "-_2") (pintype "passive"))
      (node (ref "LED4") (pin "K") (pinfunction "C_K") (pintype "passive"))
      (node (ref "TP19") (pin "TP") (pinfunction "PP_TP") (pintype "input"))
      (node (ref "X1") (pin "9") (pinfunction "9_9") (pintype "passive"))
    )
    (net (code "22") (name "Net-(2I-KL)") (class "Default")
      (node (ref "2") (pin "6") (pinfunction "KL_6") (pintype "passive"))
      (node (ref "TP21") (pin "TP") (pinfunction "PP_TP") (pintype "input"))
      (node (ref "U$2") (pin "2") (pinfunction "2_2") (pintype "passive"))
    )
    (net (code "23") (name "Net-(2J-KL)") (class "Default")
      (node (ref "2") (pin "7") (pinfunction "KL_7") (pintype "passive"))
      (node (ref "LED6") (pin "A") (pinfunction "A_A") (pintype "passive"))
      (node (ref "TP22") (pin "TP") (pinfunction "PP_TP") (pintype "input"))
      (node (ref "X1") (pin "8") (pinfunction "8_8") (pintype "passive"))
    )
    (net (code "24") (name "Net-(2K-KL)") (class "Default")
      (node (ref "2") (pin "8") (pinfunction "KL_8") (pintype "passive"))
      (node (ref "D14") (pin "2") (pinfunction "-_2") (pintype "passive"))
      (node (ref "LED7") (pin "K") (pinfunction "C_K") (pintype "passive"))
      (node (ref "TP23") (pin "TP") (pinfunction "PP_TP") (pintype "input"))
      (node (ref "X1") (pin "14") (pinfunction "14_14") (pintype "passive"))
    )
    (net (code "25") (name "Net-(2L-KL)") (class "Default")
      (node (ref "2") (pin "9") (pinfunction "KL_9") (pintype "passive"))
      (node (ref "D12") (pin "1") (pinfunction "+_1") (pintype "passive"))
      (node (ref "D2") (pin "1") (pinfunction "+_1") (pintype "passive"))
      (node (ref "JP2") (pin "1") (pinfunction "1_1") (pintype "passive"))
      (node (ref "JP4") (pin "2") (pinfunction "2_2") (pintype "passive"))
      (node (ref "TP24") (pin "TP") (pinfunction "PP_TP") (pintype "input"))
    )
    (net (code "26") (name "Net-(C2-Pad1)") (class "Default")
      (node (ref "C2") (pin "1") (pinfunction "1_1") (pintype "passive"))
      (node (ref "R10") (pin "1") (pinfunction "1_1") (pintype "passive"))
      (node (ref "R12") (pin "2") (pinfunction "2_2") (pintype "passive"))
    )
    (net (code "27") (name "Net-(C11-Pad1)") (class "Default")
      (node (ref "C11") (pin "1") (pinfunction "1_1") (pintype "passive"))
      (node (ref "R42") (pin "1") (pinfunction "1_1") (pintype "passive"))
      (node (ref "R43") (pin "1") (pinfunction "1_1") (pintype "passive"))
    )
    (net (code "28") (name "Net-(D1-+)") (class "Default")
      (node (ref "D1") (pin "1") (pinfunction "+_1") (pintype "passive"))
      (node (ref "R27") (pin "1") (pinfunction "1_1") (pintype "passive"))
    )
    (net (code "29") (name "Net-(D3-+)") (class "Default")
      (node (ref "D3") (pin "1") (pinfunction "+_1") (pintype "passive"))
      (node (ref "R33") (pin "1") (pinfunction "1_1") (pintype "passive"))
    )
    (net (code "30") (name "Net-(D3--)") (class "Default")
      (node (ref "C1") (pin "2") (pinfunction "2_2") (pintype "passive"))
      (node (ref "D3") (pin "2") (pinfunction "-_2") (pintype "passive"))
      (node (ref "IC5") (pin "2") (pinfunction "TR_2") (pintype "input"))
      (node (ref "IC5") (pin "6") (pinfunction "THR_6") (pintype "input"))
      (node (ref "R24") (pin "1") (pinfunction "1_1") (pintype "passive"))
      (node (ref "U$3") (pin "6") (pinfunction "D2_6") (pintype "passive"))
    )
    (net (code "31") (name "Net-(D5-PadC)") (class "Default")
      (node (ref "D5") (pin "C") (pinfunction "C_C") (pintype "passive"))
      (node (ref "R1") (pin "2") (pinfunction "2_2") (pintype "passive"))
      (node (ref "X1") (pin "22") (pinfunction "22_22") (pintype "passive"))
    )
    (net (code "32") (name "Net-(D8-+)") (class "Default")
      (node (ref "D8") (pin "1") (pinfunction "+_1") (pintype "passive"))
      (node (ref "R17") (pin "1") (pinfunction "1_1") (pintype "passive"))
    )
    (net (code "33") (name "Net-(D8--)") (class "Default")
      (node (ref "D8") (pin "2") (pinfunction "-_2") (pintype "passive"))
      (node (ref "IC7") (pin "2") (pinfunction "OUT_2") (pintype "open_collector"))
      (node (ref "Q10") (pin "1") (pinfunction "G_1") (pintype "passive"))
      (node (ref "R22") (pin "2") (pinfunction "2_2") (pintype "passive"))
      (node (ref "U$2") (pin "1") (pinfunction "1_1") (pintype "passive"))
    )
    (net (code "34") (name "Net-(D13-+)") (class "Default")
      (node (ref "D13") (pin "1") (pinfunction "+_1") (pintype "passive"))
      (node (ref "JP2") (pin "2") (pinfunction "2_2") (pintype "passive"))
    )
    (net (code "35") (name "Net-(D14-+)") (class "Default")
      (node (ref "D14") (pin "1") (pinfunction "+_1") (pintype "passive"))
      (node (ref "JP4") (pin "1") (pinfunction "1_1") (pintype "passive"))
    )
    (net (code "36") (name "Net-(D15--)") (class "Default")
      (node (ref "D15") (pin "2") (pinfunction "-_2") (pintype "passive"))
      (node (ref "Q1") (pin "2") (pinfunction "C_2") (pintype "passive"))
      (node (ref "Q3") (pin "2") (pinfunction "C_2") (pintype "passive"))
      (node (ref "START") (pin "TP") (pinfunction "PP_TP") (pintype "input"))
      (node (ref "X1") (pin "5") (pinfunction "5_5") (pintype "passive"))
    )
    (net (code "37") (name "Net-(IC3A-A)") (class "Default")
      (node (ref "IC3") (pin "10") (pinfunction "A_10") (pintype "input"))
      (node (ref "R31") (pin "1") (pinfunction "1_1") (pintype "passive"))
      (node (ref "U$3") (pin "1") (pinfunction "D1_1") (pintype "passive"))
      (node (ref "X1") (pin "4") (pinfunction "4_4") (pintype "passive"))
      (node (ref "X3") (pin "2") (pinfunction "S_2") (pintype "passive"))
    )
    (net (code "38") (name "Net-(IC3A-B)") (class "Default")
      (node (ref "IC3") (pin "13") (pinfunction "B_13") (pintype "input"))
      (node (ref "R30") (pin "1") (pinfunction "1_1") (pintype "passive"))
      (node (ref "U$3") (pin "4") (pinfunction "D4_4") (pintype "passive"))
      (node (ref "X1") (pin "3") (pinfunction "3_3") (pintype "passive"))
      (node (ref "X3") (pin "3") (pinfunction "S_3") (pintype "passive"))
    )
    (net (code "39") (name "Net-(IC3A-C)") (class "Default")
      (node (ref "IC3") (pin "12") (pinfunction "C_12") (pintype "input"))
      (node (ref "R29") (pin "1") (pinfunction "1_1") (pintype "passive"))
      (node (ref "U$3") (pin "3") (pinfunction "D3_3") (pintype "passive"))
      (node (ref "X1") (pin "2") (pinfunction "2_2") (pintype "passive"))
      (node (ref "X3") (pin "4") (pinfunction "S_4") (pintype "passive"))
    )
    (net (code "40") (name "Net-(IC3A-Q0)") (class "Default")
      (node (ref "IC3") (pin "3") (pinfunction "Q0_3") (pintype "output"))
      (node (ref "IC6") (pin "1") (pinfunction "I1_1") (pintype "input"))
      (node (ref "IC6") (pin "2") (pinfunction "I2_2") (pintype "input"))
      (node (ref "Q11") (pin "1") (pinfunction "G_1") (pintype "passive"))
    )
    (net (code "41") (name "Net-(IC3A-Q1)") (class "Default")
      (node (ref "IC3") (pin "14") (pinfunction "Q1_14") (pintype "output"))
      (node (ref "IC6") (pin "6") (pinfunction "I6_6") (pintype "input"))
    )
    (net (code "42") (name "Net-(IC3A-Q2)") (class "Default")
      (node (ref "IC3") (pin "2") (pinfunction "Q2_2") (pintype "output"))
      (node (ref "IC6") (pin "7") (pinfunction "I7_7") (pintype "input"))
    )
    (net (code "43") (name "Net-(IC3A-Q3)") (class "Default")
      (node (ref "IC3") (pin "15") (pinfunction "Q3_15") (pintype "output"))
      (node (ref "IC6") (pin "5") (pinfunction "I5_5") (pintype "input"))
    )
    (net (code "44") (name "Net-(IC3A-Q4)") (class "Default")
      (node (ref "IC3") (pin "1") (pinfunction "Q4_1") (pintype "output"))
      (node (ref "IC6") (pin "4") (pinfunction "I4_4") (pintype "input"))
    )
    (net (code "45") (name "Net-(IC3A-Q5)") (class "Default")
      (node (ref "IC3") (pin "6") (pinfunction "Q5_6") (pintype "output"))
      (node (ref "IC6") (pin "3") (pinfunction "I3_3") (pintype "input"))
    )
    (net (code "46") (name "Net-(IC4-ADJ)") (class "Default")
      (node (ref "IC4") (pin "1") (pinfunction "ADJ_1") (pintype "input"))
      (node (ref "R18") (pin "1") (pinfunction "1_1") (pintype "passive"))
      (node (ref "R5") (pin "2") (pinfunction "2_2") (pintype "passive"))
      (node (ref "X1") (pin "7") (pinfunction "7_7") (pintype "passive"))
    )
    (net (code "47") (name "Net-(IC4-VI)") (class "Default")
      (node (ref "IC4") (pin "3") (pinfunction "VI_3") (pintype "input"))
      (node (ref "Q2") (pin "2") (pinfunction "C_2") (pintype "passive"))
      (node (ref "Q4") (pin "2") (pinfunction "C_2") (pintype "passive"))
    )
    (net (code "48") (name "Net-(IC4-VO)") (class "Default")
      (node (ref "IC4") (pin "2") (pinfunction "VO_2") (pintype "passive"))
      (node (ref "R18") (pin "2") (pinfunction "2_2") (pintype "passive"))
    )
    (net (code "49") (name "Net-(IC5-CV)") (class "Default")
      (node (ref "IC5") (pin "5") (pinfunction "CV_5") (pintype "input"))
      (node (ref "R26") (pin "2") (pinfunction "2_2") (pintype "passive"))
    )
    (net (code "50") (name "Net-(IC5-Q)") (class "Default")
      (node (ref "IC5") (pin "3") (pinfunction "Q_3") (pintype "output"))
      (node (ref "IC8") (pin "12") (pinfunction "A_12") (pintype "input"))
      (node (ref "R26") (pin "1") (pinfunction "1_1") (pintype "passive"))
    )
    (net (code "51") (name "Net-(IC6-O1)") (class "Default")
      (node (ref "IC6") (pin "16") (pinfunction "O1_16") (pintype "open_collector"))
      (node (ref "Q9") (pin "2") (pinfunction "C_2") (pintype "passive"))
      (node (ref "R3") (pin "2") (pinfunction "2_2") (pintype "passive"))
      (node (ref "T3") (pin "C") (pinfunction "C_C") (pintype "passive"))
      (node (ref "X1") (pin "21") (pinfunction "21_21") (pintype "passive"))
    )
    (net (code "52") (name "Net-(IC6-O2)") (class "Default")
      (node (ref "IC6") (pin "15") (pinfunction "O2_15") (pintype "open_collector"))
      (node (ref "R13") (pin "1") (pinfunction "1_1") (pintype "passive"))
    )
    (net (code "53") (name "Net-(IC7A-+IN)") (class "Default")
      (node (ref "IC7") (pin "5") (pinfunction "+IN_5") (pintype "input"))
      (node (ref "R15") (pin "1") (pinfunction "1_1") (pintype "passive"))
      (node (ref "R16") (pin "2") (pinfunction "2_2") (pintype "passive"))
      (node (ref "R17") (pin "2") (pinfunction "2_2") (pintype "passive"))
    )
    (net (code "54") (name "Net-(IC7A--IN)") (class "Default")
      (node (ref "C3") (pin "1") (pinfunction "1_1") (pintype "passive"))
      (node (ref "IC7") (pin "4") (pinfunction "-IN_4") (pintype "input"))
      (node (ref "R12") (pin "1") (pinfunction "1_1") (pintype "passive"))
    )
    (net (code "55") (name "Net-(IC7B-+IN)") (class "Default")
      (node (ref "IC7") (pin "7") (pinfunction "+IN_7") (pintype "input"))
      (node (ref "R25") (pin "1") (pinfunction "1_1") (pintype "passive"))
      (node (ref "R6") (pin "1") (pinfunction "1_1") (pintype "passive"))
    )
    (net (code "56") (name "Net-(IC7B--IN)") (class "Default")
      (node (ref "IC7") (pin "6") (pinfunction "-IN_6") (pintype "input"))
      (node (ref "IC7") (pin "8") (pinfunction "-IN_8") (pintype "input"))
      (node (ref "R5") (pin "1") (pinfunction "1_1") (pintype "passive"))
    )
    (net (code "57") (name "Net-(IC7B-OUT)") (class "Default")
      (node (ref "IC7") (pin "1") (pinfunction "OUT_1") (pintype "open_collector"))
      (node (ref "R10") (pin "2") (pinfunction "2_2") (pintype "passive"))
      (node (ref "R19") (pin "2") (pinfunction "2_2") (pintype "passive"))
    )
    (net (code "58") (name "Net-(IC7C-+IN)") (class "Default")
      (node (ref "C5") (pin "1") (pinfunction "1_1") (pintype "passive"))
      (node (ref "IC7") (pin "9") (pinfunction "+IN_9") (pintype "input"))
      (node (ref "R25") (pin "2") (pinfunction "2_2") (pintype "passive"))
      (node (ref "R8") (pin "2") (pinfunction "2_2") (pintype "passive"))
    )
    (net (code "59") (name "Net-(IC7C-OUT)") (class "Default")
      (node (ref "C9") (pin "2") (pinfunction "2_2") (pintype "passive"))
      (node (ref "IC7") (pin "14") (pinfunction "OUT_14") (pintype "open_collector"))
      (node (ref "R9") (pin "2") (pinfunction "2_2") (pintype "passive"))
    )
    (net (code "60") (name "Net-(IC8B-B)") (class "Default")
      (node (ref "IC8") (pin "11") (pinfunction "B_11") (pintype "input"))
      (node (ref "IC8") (pin "9") (pinfunction "~{Q}_9") (pintype "output"))
      (node (ref "R35") (pin "2") (pinfunction "2_2") (pintype "passive"))
    )
    (net (code "61") (name "Net-(IC8B-T2)") (class "Default")
      (node (ref "C10") (pin "1") (pinfunction "1_1") (pintype "passive"))
      (node (ref "IC8") (pin "14") (pinfunction "T2_14") (pintype "input"))
      (node (ref "R34") (pin "1") (pinfunction "1_1") (pintype "passive"))
    )
    (net (code "62") (name "Net-(IC10A-+IN)") (class "Default")
      (node (ref "C8") (pin "1") (pinfunction "1_1") (pintype "passive"))
      (node (ref "IC10") (pin "3") (pinfunction "+IN_3") (pintype "input"))
      (node (ref "R1") (pin "1") (pinfunction "1_1") (pintype "passive"))
    )
    (net (code "63") (name "Net-(IC10A--IN)") (class "Default")
      (node (ref "IC10") (pin "2") (pinfunction "-IN_2") (pintype "input"))
      (node (ref "R2") (pin "2") (pinfunction "2_2") (pintype "passive"))
    )
    (net (code "64") (name "Net-(IC10A-OUT)") (class "Default")
      (node (ref "IC10") (pin "1") (pinfunction "OUT_1") (pintype "output"))
      (node (ref "R42") (pin "2") (pinfunction "2_2") (pintype "passive"))
    )
    (net (code "65") (name "Net-(IC10B-+IN)") (class "Default")
      (node (ref "IC10") (pin "5") (pinfunction "+IN_5") (pintype "input"))
      (node (ref "R43") (pin "2") (pinfunction "2_2") (pintype "passive"))
      (node (ref "R44") (pin "2") (pinfunction "2_2") (pintype "passive"))
    )
    (net (code "66") (name "Net-(IC10B--IN)") (class "Default")
      (node (ref "IC10") (pin "6") (pinfunction "-IN_6") (pintype "input"))
      (node (ref "R45") (pin "1") (pinfunction "1_1") (pintype "passive"))
      (node (ref "R46") (pin "2") (pinfunction "2_2") (pintype "passive"))
    )
    (net (code "67") (name "Net-(IC10B-OUT)") (class "Default")
      (node (ref "IC10") (pin "7") (pinfunction "OUT_7") (pintype "output"))
      (node (ref "R32") (pin "1") (pinfunction "1_1") (pintype "passive"))
      (node (ref "R44") (pin "1") (pinfunction "1_1") (pintype "passive"))
    )
    (net (code "68") (name "Net-(JP1-Pad2)") (class "Default")
      (node (ref "JP1") (pin "2") (pinfunction "2_2") (pintype "passive"))
      (node (ref "R36") (pin "2") (pinfunction "2_2") (pintype "passive"))
      (node (ref "R37") (pin "2") (pinfunction "2_2") (pintype "passive"))
      (node (ref "SJ1") (pin "2") (pinfunction "2_2") (pintype "passive"))
    )
    (net (code "69") (name "Net-(JP3-Pad1)") (class "Default")
      (node (ref "JP3") (pin "1") (pinfunction "1_1") (pintype "passive"))
      (node (ref "R23") (pin "2") (pinfunction "2_2") (pintype "passive"))
    )
    (net (code "70") (name "Net-(LED1-PadA)") (class "Default")
      (node (ref "LED1") (pin "A") (pinfunction "A_A") (pintype "passive"))
      (node (ref "LED2") (pin "A") (pinfunction "A_A") (pintype "passive"))
      (node (ref "LED3") (pin "A") (pinfunction "A_A") (pintype "passive"))
      (node (ref "LED4") (pin "A") (pinfunction "A_A") (pintype "passive"))
      (node (ref "LED7") (pin "A") (pinfunction "A_A") (pintype "passive"))
      (node (ref "R11") (pin "1") (pinfunction "1_1") (pintype "passive"))
    )
    (net (code "71") (name "Net-(LED6-C)") (class "Default")
      (node (ref "LED6") (pin "K") (pinfunction "C_K") (pintype "passive"))
      (node (ref "R4") (pin "1") (pinfunction "1_1") (pintype "passive"))
    )
    (net (code "72") (name "Net-(Q1-B)") (class "Default")
      (node (ref "Q1") (pin "1") (pinfunction "B_1") (pintype "passive"))
      (node (ref "Q3") (pin "1") (pinfunction "B_1") (pintype "passive"))
      (node (ref "R13") (pin "2") (pinfunction "2_2") (pintype "passive"))
    )
    (net (code "73") (name "Net-(Q2-B)") (class "Default")
      (node (ref "Q2") (pin "1") (pinfunction "B_1") (pintype "passive"))
      (node (ref "Q4") (pin "1") (pinfunction "B_1") (pintype "passive"))
      (node (ref "R9") (pin "1") (pinfunction "1_1") (pintype "passive"))
    )
    (net (code "74") (name "Net-(Q5-B)") (class "Default")
      (node (ref "Q5") (pin "1") (pinfunction "B_1") (pintype "passive"))
      (node (ref "Q6") (pin "1") (pinfunction "B_1") (pintype "passive"))
      (node (ref "Q6") (pin "2") (pinfunction "C_2") (pintype "passive"))
      (node (ref "Q7") (pin "1") (pinfunction "B_1") (pintype "passive"))
      (node (ref "Q7") (pin "2") (pinfunction "C_2") (pintype "passive"))
      (node (ref "Q8") (pin "1") (pinfunction "B_1") (pintype "passive"))
      (node (ref "R38") (pin "1") (pinfunction "1_1") (pintype "passive"))
      (node (ref "R39") (pin "1") (pinfunction "1_1") (pintype "passive"))
      (node (ref "T1") (pin "2") (pinfunction "B_2") (pintype "passive"))
      (node (ref "T1") (pin "4") (pinfunction "B_4") (pintype "passive"))
      (node (ref "T1") (pin "6") (pinfunction "C1_6") (pintype "passive"))
      (node (ref "X2") (pin "2") (pinfunction "S_2") (pintype "passive"))
    )
    (net (code "75") (name "Net-(Q5-E)") (class "Default")
      (node (ref "Q5") (pin "3") (pinfunction "E_3") (pintype "passive"))
      (node (ref "Q8") (pin "3") (pinfunction "E_3") (pintype "passive"))
      (node (ref "R21") (pin "2") (pinfunction "2_2") (pintype "passive"))
      (node (ref "T1") (pin "1") (pinfunction "E_1") (pintype "passive"))
    )
    (net (code "76") (name "Net-(Q6-E)") (class "Default")
      (node (ref "Q6") (pin "3") (pinfunction "E_3") (pintype "passive"))
      (node (ref "Q7") (pin "3") (pinfunction "E_3") (pintype "passive"))
      (node (ref "R20") (pin "2") (pinfunction "2_2") (pintype "passive"))
      (node (ref "T1") (pin "3") (pinfunction "E_3") (pintype "passive"))
    )
    (net (code "77") (name "Net-(Q9-B)") (class "Default")
      (node (ref "Q9") (pin "1") (pinfunction "B_1") (pintype "passive"))
      (node (ref "R32") (pin "2") (pinfunction "2_2") (pintype "passive"))
      (node (ref "T3") (pin "B") (pinfunction "B_B") (pintype "passive"))
    )
    (net (code "78") (name "Net-(Q10-D)") (class "Default")
      (node (ref "Q10") (pin "3") (pinfunction "D_3") (pintype "passive"))
      (node (ref "R7") (pin "2") (pinfunction "2_2") (pintype "passive"))
    )
    (net (code "79") (name "Net-(R14-Pad1)") (class "Default")
      (node (ref "R14") (pin "1") (pinfunction "1_1") (pintype "passive"))
      (node (ref "R7") (pin "1") (pinfunction "1_1") (pintype "passive"))
      (node (ref "U$2") (pin "3") (pinfunction "3_3") (pintype "passive"))
    )
    (net (code "80") (name "Net-(R27-Pad2)") (class "Default")
      (node (ref "R27") (pin "2") (pinfunction "2_2") (pintype "passive"))
      (node (ref "R28") (pin "1") (pinfunction "1_1") (pintype "passive"))
    )
    (net (code "81") (name "Net-(R33-Pad2)") (class "Default")
      (node (ref "R33") (pin "2") (pinfunction "2_2") (pintype "passive"))
      (node (ref "X1") (pin "16") (pinfunction "16_16") (pintype "passive"))
    )
    (net (code "82") (name "VCC") (class "Default")
      (node (ref "6V") (pin "TP") (pinfunction "PP_TP") (pintype "input"))
      (node (ref "C4") (pin "1") (pinfunction "1_1") (pintype "passive"))
      (node (ref "IC1") (pin "OUT") (pinfunction "OUT_OUT") (pintype "passive"))
      (node (ref "IC10") (pin "8") (pinfunction "V+_8") (pintype "power_in"))
      (node (ref "IC2") (pin "1") (pinfunction "OUT_1") (pintype "passive"))
      (node (ref "IC7") (pin "3") (pinfunction "V+_3") (pintype "power_in"))
      (node (ref "R11") (pin "2") (pinfunction "2_2") (pintype "passive"))
      (node (ref "R15") (pin "2") (pinfunction "2_2") (pintype "passive"))
      (node (ref "R19") (pin "1") (pinfunction "1_1") (pintype "passive"))
      (node (ref "R45") (pin "2") (pinfunction "2_2") (pintype "passive"))
      (node (ref "R6") (pin "2") (pinfunction "2_2") (pintype "passive"))
    )
    (net (code "83") (name "unconnected-(IC3A-Q6-Pad7)") (class "Default")
      (node (ref "IC3") (pin "7") (pinfunction "Q6_7") (pintype "output"))
    )
    (net (code "84") (name "unconnected-(IC3A-Q7-Pad4)") (class "Default")
      (node (ref "IC3") (pin "4") (pinfunction "Q7_4") (pintype "output"))
    )
    (net (code "85") (name "unconnected-(IC3A-Q8-Pad9)") (class "Default")
      (node (ref "IC3") (pin "9") (pinfunction "Q8_9") (pintype "output"))
    )
    (net (code "86") (name "unconnected-(IC3A-Q9-Pad5)") (class "Default")
      (node (ref "IC3") (pin "5") (pinfunction "Q9_5") (pintype "output"))
    )
    (net (code "87") (name "unconnected-(IC5-DIS-Pad7)") (class "Default")
      (node (ref "IC5") (pin "7") (pinfunction "DIS_7") (pintype "input"))
    )
    (net (code "88") (name "unconnected-(IC7D-OUT-Pad13)") (class "Default")
      (node (ref "IC7") (pin "13") (pinfunction "OUT_13") (pintype "open_collector"))
    )
    (net (code "89") (name "unconnected-(IC8A-Q-Pad6)") (class "Default")
      (node (ref "IC8") (pin "6") (pinfunction "Q_6") (pintype "output"))
    )
    (net (code "90") (name "unconnected-(IC8A-T2-Pad2)") (class "Default")
      (node (ref "IC8") (pin "2") (pinfunction "T2_2") (pintype "input"))
    )
    (net (code "91") (name "unconnected-(IC8A-~{Q}-Pad7)") (class "Default")
      (node (ref "IC8") (pin "7") (pinfunction "~{Q}_7") (pintype "output"))
    )
    (net (code "92") (name "unconnected-(IC8B-Q-Pad10)") (class "Default")
      (node (ref "IC8") (pin "10") (pinfunction "Q_10") (pintype "output"))
    )
    (net (code "93") (name "unconnected-(Q3-C{slash}-Pad4)") (class "Default")
      (node (ref "Q3") (pin "4") (pinfunction "C/_4") (pintype "passive"))
    )
    (net (code "94") (name "unconnected-(Q4-C{slash}-Pad4)") (class "Default")
      (node (ref "Q4") (pin "4") (pinfunction "C/_4") (pintype "passive"))
    )
    (net (code "95") (name "unconnected-(Q5-C{slash}-Pad4)") (class "Default")
      (node (ref "Q5") (pin "4") (pinfunction "C/_4") (pintype "passive"))
    )
    (net (code "96") (name "unconnected-(Q6-C{slash}-Pad4)") (class "Default")
      (node (ref "Q6") (pin "4") (pinfunction "C/_4") (pintype "passive"))
    )
    (net (code "97") (name "unconnected-(T1A-C-Pad5)") (class "Default")
      (node (ref "T1") (pin "5") (pinfunction "C_5") (pintype "passive"))
    )
    (net (code "98") (name "unconnected-(T1B-C-Pad7)") (class "Default")
      (node (ref "T1") (pin "7") (pinfunction "C_7") (pintype "passive"))
    )
    (net (code "99") (name "unconnected-(X1-Pad20)") (class "Default")
      (node (ref "X1") (pin "20") (pinfunction "20_20") (pintype "passive"))
    )
    (net (code "100") (name "unconnected-(X1-Pad24)") (class "Default")
      (node (ref "X1") (pin "24") (pinfunction "24_24") (pintype "passive"))
    )
  )
)
